# h2oiq_rev1.net
KiCad netlist of a schematic drawn in EAGLE
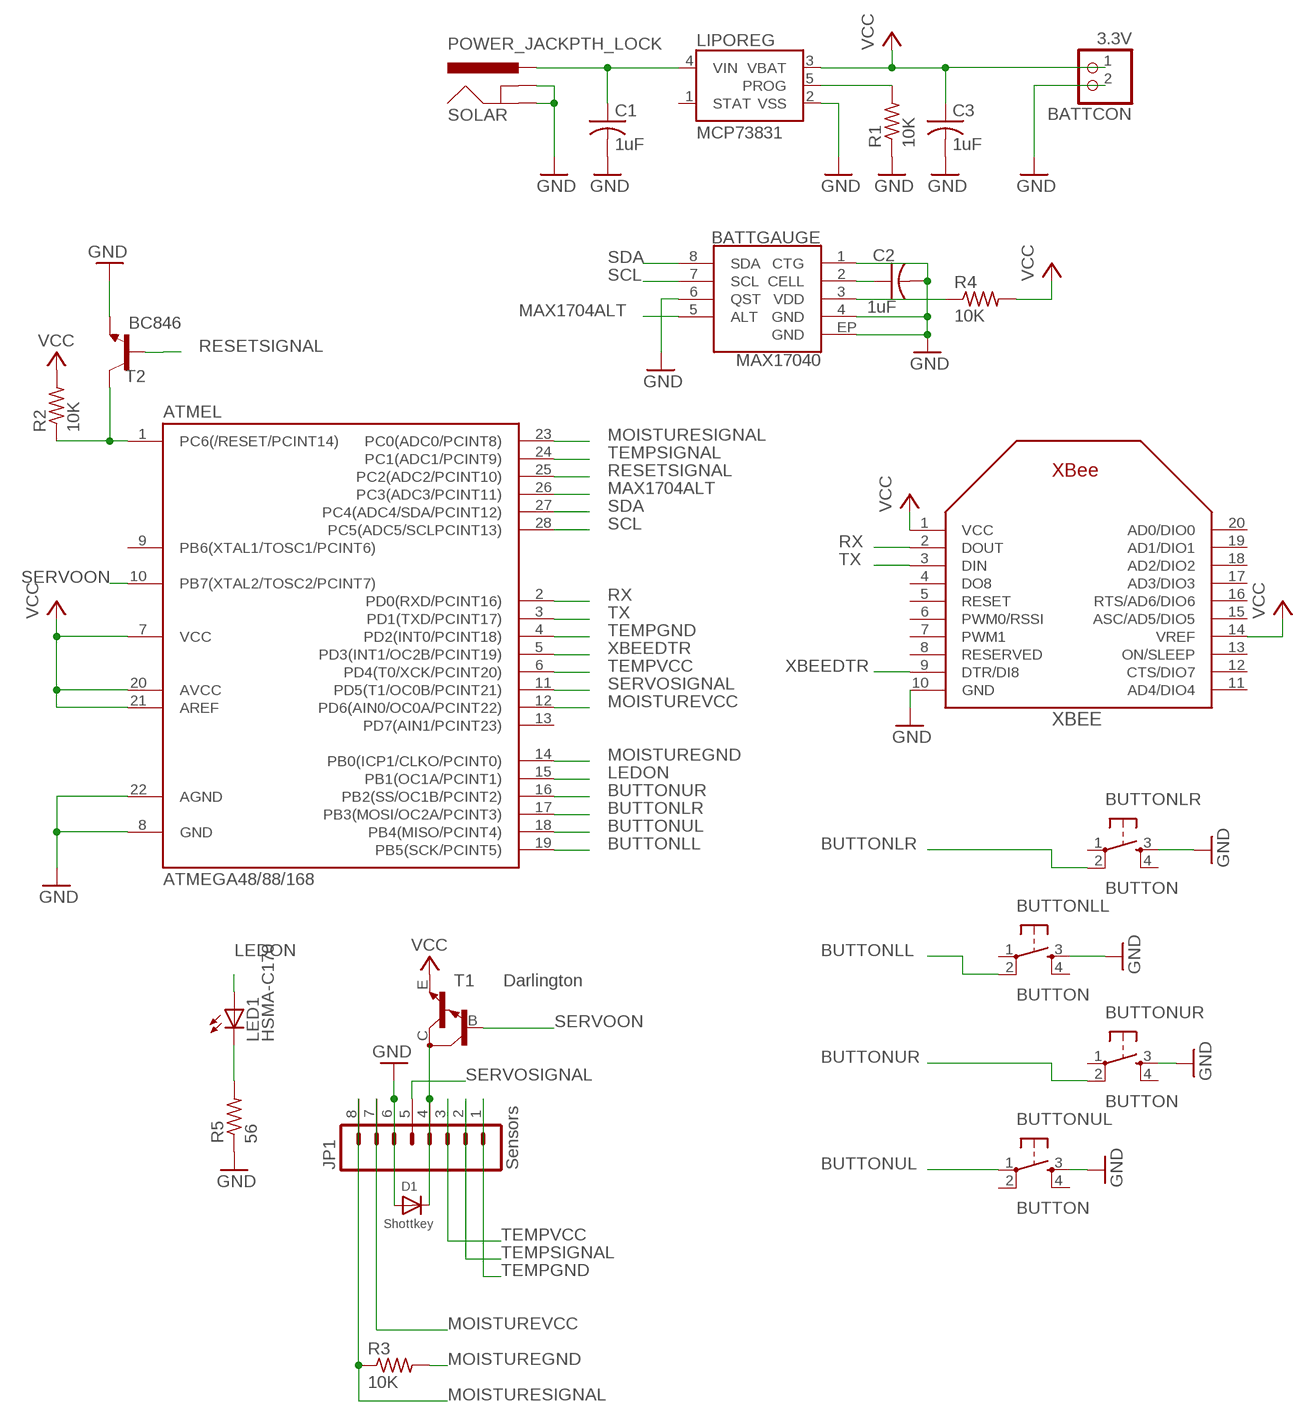
[diagram p0: schematic, sheet 1]

(export (version "E")
  (design (tool "Eeschema 10.0.6"))
  (components
    (comp (ref "ATMEL")
      (value "ATMEGA48/88/168")
      (footprint "eagle-import:DIL28-3")
      (libsource (lib "eagle-import") (part "MEGA48/88/168-PU"))
    )
    (comp (ref "BATTCON")
      (value "3.3V")
      (footprint "eagle-import:JST-PH-2-THM")
      (libsource (lib "eagle-import") (part "JST_2PIN-THM"))
    )
    (comp (ref "BATTGAUGE")
      (value "MAX17040")
      (footprint "eagle-import:MAX17040-TFDN")
      (libsource (lib "eagle-import") (part "MAX17040"))
    )
    (comp (ref "BUTTONLL")
      (value "BUTTON")
      (footprint "eagle-import:TACTILE-PTH")
      (libsource (lib "eagle-import") (part "TAC_SWITCHPTH"))
    )
    (comp (ref "BUTTONLR")
      (value "BUTTON")
      (footprint "eagle-import:TACTILE-PTH")
      (libsource (lib "eagle-import") (part "TAC_SWITCHPTH"))
    )
    (comp (ref "BUTTONUL")
      (value "BUTTON")
      (footprint "eagle-import:TACTILE-PTH")
      (libsource (lib "eagle-import") (part "TAC_SWITCHPTH"))
    )
    (comp (ref "BUTTONUR")
      (value "BUTTON")
      (footprint "eagle-import:TACTILE-PTH")
      (libsource (lib "eagle-import") (part "TAC_SWITCHPTH"))
    )
    (comp (ref "C1")
      (value "1uF")
      (footprint "eagle-import:C0603K")
      (libsource (lib "eagle-import") (part "C-USC0603K"))
    )
    (comp (ref "C2")
      (value "1uF")
      (footprint "eagle-import:C0603K")
      (libsource (lib "eagle-import") (part "C-USC0603K"))
    )
    (comp (ref "C3")
      (value "1uF")
      (footprint "eagle-import:C0603K")
      (libsource (lib "eagle-import") (part "C-USC0603K"))
    )
    (comp (ref "D1")
      (value "Shottkey")
      (footprint "eagle-import:SMADIODE")
      (libsource (lib "eagle-import") (part "DIODESMA"))
    )
    (comp (ref "JP1")
      (value "Sensors")
      (footprint "eagle-import:1X08")
      (libsource (lib "eagle-import") (part "M081X08"))
    )
    (comp (ref "LED1")
      (value "HSMA-C170")
      (footprint "eagle-import:LED-HSMA-SMD")
      (libsource (lib "eagle-import") (part "LED-HSMA-C170"))
    )
    (comp (ref "LIPOREG")
      (value "MCP73831")
      (footprint "eagle-import:SOT23-5")
      (libsource (lib "eagle-import") (part "MCP73831"))
    )
    (comp (ref "R1")
      (value "10K")
      (footprint "eagle-import:R0805")
      (libsource (lib "eagle-import") (part "R-US_R0805"))
    )
    (comp (ref "R2")
      (value "10K")
      (footprint "eagle-import:R0805")
      (libsource (lib "eagle-import") (part "R-US_R0805"))
    )
    (comp (ref "R3")
      (value "10K")
      (footprint "eagle-import:R0805")
      (libsource (lib "eagle-import") (part "R-US_R0805"))
    )
    (comp (ref "R4")
      (value "10K")
      (footprint "eagle-import:R0805")
      (libsource (lib "eagle-import") (part "R-US_R0805"))
    )
    (comp (ref "R5")
      (value "56")
      (footprint "eagle-import:R0805")
      (libsource (lib "eagle-import") (part "R-US_R0805"))
    )
    (comp (ref "SOLAR")
      (value "POWER_JACKPTH_LOCK")
      (footprint "eagle-import:POWER_JACK_PTH_LOCK")
      (libsource (lib "eagle-import") (part "POWER_JACKPTH_LOCK"))
    )
    (comp (ref "T1")
      (value "Darlington")
      (footprint "eagle-import:SOT23-BEC")
      (libsource (lib "eagle-import") (part "-NPN_DARL-SOT23-BECMMBTA13LT1"))
    )
    (comp (ref "T2")
      (value "BC846")
      (footprint "eagle-import:SOT23")
      (libsource (lib "eagle-import") (part "BC846"))
    )
    (comp (ref "XBEE")
      (value "XBEE")
      (footprint "eagle-import:XBEE")
      (libsource (lib "eagle-import") (part "XBEE"))
    )
  )
  (nets
    (net (code "1") (name "/BUTTONLL") (class "Default")
      (node (ref "ATMEL") (pin "19") (pinfunction "PB5(SCK/PCINT5)_19") (pintype "bidirectional"))
      (node (ref "BUTTONLL") (pin "2") (pinfunction "2_2") (pintype "passive"))
    )
    (net (code "2") (name "/BUTTONLR") (class "Default")
      (node (ref "ATMEL") (pin "17") (pinfunction "PB3(MOSI/OC2A/PCINT3)_17") (pintype "bidirectional"))
      (node (ref "BUTTONLR") (pin "2") (pinfunction "2_2") (pintype "passive"))
    )
    (net (code "3") (name "/BUTTONUL") (class "Default")
      (node (ref "ATMEL") (pin "18") (pinfunction "PB4(MISO/PCINT4)_18") (pintype "bidirectional"))
      (node (ref "BUTTONUL") (pin "1") (pinfunction "1_1") (pintype "passive"))
    )
    (net (code "4") (name "/BUTTONUR") (class "Default")
      (node (ref "ATMEL") (pin "16") (pinfunction "PB2(SS/OC1B/PCINT2)_16") (pintype "bidirectional"))
      (node (ref "BUTTONUR") (pin "2") (pinfunction "2_2") (pintype "passive"))
    )
    (net (code "5") (name "/LEDON") (class "Default")
      (node (ref "ATMEL") (pin "15") (pinfunction "PB1(OC1A/PCINT1)_15") (pintype "bidirectional"))
      (node (ref "LED1") (pin "P$1") (pinfunction "A_P$1") (pintype "passive"))
    )
    (net (code "6") (name "/MAX1704ALT") (class "Default")
      (node (ref "ATMEL") (pin "26") (pinfunction "PC3(ADC3/PCINT11)_26") (pintype "bidirectional"))
      (node (ref "BATTGAUGE") (pin "5") (pinfunction "ALT_5") (pintype "bidirectional"))
    )
    (net (code "7") (name "/MOISTUREGND") (class "Default")
      (node (ref "ATMEL") (pin "14") (pinfunction "PB0(ICP1/CLKO/PCINT0)_14") (pintype "bidirectional"))
      (node (ref "R3") (pin "2") (pinfunction "2_2") (pintype "passive"))
    )
    (net (code "8") (name "/MOISTURESIGNAL") (class "Default")
      (node (ref "ATMEL") (pin "23") (pinfunction "PC0(ADC0/PCINT8)_23") (pintype "bidirectional"))
      (node (ref "JP1") (pin "8") (pinfunction "8_8") (pintype "passive"))
      (node (ref "R3") (pin "1") (pinfunction "1_1") (pintype "passive"))
    )
    (net (code "9") (name "/MOISTUREVCC") (class "Default")
      (node (ref "ATMEL") (pin "12") (pinfunction "PD6(AIN0/OC0A/PCINT22)_12") (pintype "bidirectional"))
      (node (ref "JP1") (pin "7") (pinfunction "7_7") (pintype "passive"))
    )
    (net (code "10") (name "/RESETSIGNAL") (class "Default")
      (node (ref "ATMEL") (pin "25") (pinfunction "PC2(ADC2/PCINT10)_25") (pintype "bidirectional"))
      (node (ref "T2") (pin "1") (pinfunction "B_1") (pintype "passive"))
    )
    (net (code "11") (name "/RX") (class "Default")
      (node (ref "ATMEL") (pin "2") (pinfunction "PD0(RXD/PCINT16)_2") (pintype "bidirectional"))
      (node (ref "XBEE") (pin "2") (pinfunction "DOUT_2") (pintype "output"))
    )
    (net (code "12") (name "/SCL") (class "Default")
      (node (ref "ATMEL") (pin "28") (pinfunction "PC5(ADC5/SCLPCINT13)_28") (pintype "bidirectional"))
      (node (ref "BATTGAUGE") (pin "7") (pinfunction "SCL_7") (pintype "bidirectional"))
    )
    (net (code "13") (name "/SDA") (class "Default")
      (node (ref "ATMEL") (pin "27") (pinfunction "PC4(ADC4/SDA/PCINT12)_27") (pintype "bidirectional"))
      (node (ref "BATTGAUGE") (pin "8") (pinfunction "SDA_8") (pintype "bidirectional"))
    )
    (net (code "14") (name "/SERVOON") (class "Default")
      (node (ref "ATMEL") (pin "10") (pinfunction "PB7(XTAL2/TOSC2/PCINT7)_10") (pintype "bidirectional"))
      (node (ref "T1") (pin "B") (pinfunction "B_B") (pintype "passive"))
    )
    (net (code "15") (name "/SERVOSIGNAL") (class "Default")
      (node (ref "ATMEL") (pin "11") (pinfunction "PD5(T1/OC0B/PCINT21)_11") (pintype "bidirectional"))
      (node (ref "JP1") (pin "5") (pinfunction "5_5") (pintype "passive"))
    )
    (net (code "16") (name "/TEMPGND") (class "Default")
      (node (ref "ATMEL") (pin "4") (pinfunction "PD2(INT0/PCINT18)_4") (pintype "bidirectional"))
      (node (ref "JP1") (pin "1") (pinfunction "1_1") (pintype "passive"))
    )
    (net (code "17") (name "/TEMPSIGNAL") (class "Default")
      (node (ref "ATMEL") (pin "24") (pinfunction "PC1(ADC1/PCINT9)_24") (pintype "bidirectional"))
      (node (ref "JP1") (pin "2") (pinfunction "2_2") (pintype "passive"))
    )
    (net (code "18") (name "/TEMPVCC") (class "Default")
      (node (ref "ATMEL") (pin "6") (pinfunction "PD4(T0/XCK/PCINT20)_6") (pintype "bidirectional"))
      (node (ref "JP1") (pin "3") (pinfunction "3_3") (pintype "passive"))
    )
    (net (code "19") (name "/TX") (class "Default")
      (node (ref "ATMEL") (pin "3") (pinfunction "PD1(TXD/PCINT17)_3") (pintype "bidirectional"))
      (node (ref "XBEE") (pin "3") (pinfunction "DIN_3") (pintype "input"))
    )
    (net (code "20") (name "/XBEEDTR") (class "Default")
      (node (ref "ATMEL") (pin "5") (pinfunction "PD3(INT1/OC2B/PCINT19)_5") (pintype "bidirectional"))
      (node (ref "XBEE") (pin "9") (pinfunction "DTR/DI8_9") (pintype "input"))
    )
    (net (code "21") (name "GND") (class "Default")
      (node (ref "ATMEL") (pin "22") (pinfunction "AGND_22") (pintype "power_in"))
      (node (ref "ATMEL") (pin "8") (pinfunction "GND_8") (pintype "power_in"))
      (node (ref "BATTCON") (pin "2") (pinfunction "1_2") (pintype "passive"))
      (node (ref "BATTGAUGE") (pin "1") (pinfunction "CTG_1") (pintype "bidirectional"))
      (node (ref "BATTGAUGE") (pin "4") (pinfunction "GND_4") (pintype "bidirectional"))
      (node (ref "BATTGAUGE") (pin "6") (pinfunction "QST_6") (pintype "bidirectional"))
      (node (ref "BATTGAUGE") (pin "EP") (pinfunction "GND_EP") (pintype "bidirectional"))
      (node (ref "BUTTONLL") (pin "3") (pinfunction "3_3") (pintype "passive"))
      (node (ref "BUTTONLR") (pin "3") (pinfunction "3_3") (pintype "passive"))
      (node (ref "BUTTONUL") (pin "3") (pinfunction "3_3") (pintype "passive"))
      (node (ref "BUTTONUR") (pin "3") (pinfunction "3_3") (pintype "passive"))
      (node (ref "C1") (pin "2") (pinfunction "2_2") (pintype "passive"))
      (node (ref "C2") (pin "2") (pinfunction "2_2") (pintype "passive"))
      (node (ref "C3") (pin "2") (pinfunction "2_2") (pintype "passive"))
      (node (ref "D1") (pin "A") (pinfunction "A_A") (pintype "passive"))
      (node (ref "JP1") (pin "6") (pinfunction "6_6") (pintype "passive"))
      (node (ref "LIPOREG") (pin "2") (pinfunction "VSS_2") (pintype "power_in"))
      (node (ref "R1") (pin "1") (pinfunction "1_1") (pintype "passive"))
      (node (ref "R5") (pin "1") (pinfunction "1_1") (pintype "passive"))
      (node (ref "SOLAR") (pin "GND") (pinfunction "GND_GND") (pintype "bidirectional"))
      (node (ref "SOLAR") (pin "GNDBREAK") (pinfunction "GNDBREAK_GNDBREAK") (pintype "bidirectional"))
      (node (ref "T2") (pin "2") (pinfunction "E_2") (pintype "passive"))
      (node (ref "XBEE") (pin "10") (pinfunction "GND_10") (pintype "power_in"))
    )
    (net (code "22") (name "Net-(ATMEL-PC6({slash}RESET{slash}PCINT14))") (class "Default")
      (node (ref "ATMEL") (pin "1") (pinfunction "PC6(/RESET/PCINT14)_1") (pintype "bidirectional"))
      (node (ref "R2") (pin "1") (pinfunction "1_1") (pintype "passive"))
      (node (ref "T2") (pin "3") (pinfunction "C_3") (pintype "passive"))
    )
    (net (code "23") (name "Net-(BATTGAUGE-CELL)") (class "Default")
      (node (ref "BATTGAUGE") (pin "2") (pinfunction "CELL_2") (pintype "bidirectional"))
      (node (ref "C2") (pin "1") (pinfunction "1_1") (pintype "passive"))
    )
    (net (code "24") (name "Net-(BATTGAUGE-VDD)") (class "Default")
      (node (ref "BATTGAUGE") (pin "3") (pinfunction "VDD_3") (pintype "bidirectional"))
      (node (ref "R4") (pin "1") (pinfunction "1_1") (pintype "passive"))
    )
    (net (code "25") (name "Net-(D1-PadC)") (class "Default")
      (node (ref "D1") (pin "C") (pinfunction "C_C") (pintype "passive"))
      (node (ref "JP1") (pin "4") (pinfunction "4_4") (pintype "passive"))
      (node (ref "T1") (pin "C") (pinfunction "C_C") (pintype "passive"))
    )
    (net (code "26") (name "Net-(LED1-C)") (class "Default")
      (node (ref "LED1") (pin "P$2") (pinfunction "C_P$2") (pintype "passive"))
      (node (ref "R5") (pin "2") (pinfunction "2_2") (pintype "passive"))
    )
    (net (code "27") (name "Net-(LIPOREG-PROG)") (class "Default")
      (node (ref "LIPOREG") (pin "5") (pinfunction "PROG_5") (pintype "input"))
      (node (ref "R1") (pin "2") (pinfunction "2_2") (pintype "passive"))
    )
    (net (code "28") (name "Net-(LIPOREG-VIN)") (class "Default")
      (node (ref "C1") (pin "1") (pinfunction "1_1") (pintype "passive"))
      (node (ref "LIPOREG") (pin "4") (pinfunction "VIN_4") (pintype "power_in"))
      (node (ref "SOLAR") (pin "PWR") (pinfunction "PWR_PWR") (pintype "bidirectional"))
    )
    (net (code "29") (name "VCC") (class "Default")
      (node (ref "ATMEL") (pin "20") (pinfunction "AVCC_20") (pintype "passive"))
      (node (ref "ATMEL") (pin "21") (pinfunction "AREF_21") (pintype "passive"))
      (node (ref "ATMEL") (pin "7") (pinfunction "VCC_7") (pintype "power_in"))
      (node (ref "BATTCON") (pin "1") (pinfunction "2_1") (pintype "passive"))
      (node (ref "C3") (pin "1") (pinfunction "1_1") (pintype "passive"))
      (node (ref "LIPOREG") (pin "3") (pinfunction "VBAT_3") (pintype "power_in"))
      (node (ref "R2") (pin "2") (pinfunction "2_2") (pintype "passive"))
      (node (ref "R4") (pin "2") (pinfunction "2_2") (pintype "passive"))
      (node (ref "T1") (pin "E") (pinfunction "E_E") (pintype "passive"))
      (node (ref "XBEE") (pin "1") (pinfunction "VCC_1") (pintype "power_in"))
      (node (ref "XBEE") (pin "14") (pinfunction "VREF_14") (pintype "input"))
    )
    (net (code "30") (name "unconnected-(ATMEL-PB6(XTAL1{slash}TOSC1{slash}PCINT6)-Pad9)") (class "Default")
      (node (ref "ATMEL") (pin "9") (pinfunction "PB6(XTAL1/TOSC1/PCINT6)_9") (pintype "bidirectional"))
    )
    (net (code "31") (name "unconnected-(ATMEL-PD7(AIN1{slash}PCINT23)-Pad13)") (class "Default")
      (node (ref "ATMEL") (pin "13") (pinfunction "PD7(AIN1/PCINT23)_13") (pintype "bidirectional"))
    )
    (net (code "32") (name "unconnected-(BUTTONLL-Pad1)") (class "Default")
      (node (ref "BUTTONLL") (pin "1") (pinfunction "1_1") (pintype "passive"))
    )
    (net (code "33") (name "unconnected-(BUTTONLL-Pad4)") (class "Default")
      (node (ref "BUTTONLL") (pin "4") (pinfunction "4_4") (pintype "passive"))
    )
    (net (code "34") (name "unconnected-(BUTTONLR-Pad1)") (class "Default")
      (node (ref "BUTTONLR") (pin "1") (pinfunction "1_1") (pintype "passive"))
    )
    (net (code "35") (name "unconnected-(BUTTONLR-Pad4)") (class "Default")
      (node (ref "BUTTONLR") (pin "4") (pinfunction "4_4") (pintype "passive"))
    )
    (net (code "36") (name "unconnected-(BUTTONUL-Pad2)") (class "Default")
      (node (ref "BUTTONUL") (pin "2") (pinfunction "2_2") (pintype "passive"))
    )
    (net (code "37") (name "unconnected-(BUTTONUL-Pad4)") (class "Default")
      (node (ref "BUTTONUL") (pin "4") (pinfunction "4_4") (pintype "passive"))
    )
    (net (code "38") (name "unconnected-(BUTTONUR-Pad1)") (class "Default")
      (node (ref "BUTTONUR") (pin "1") (pinfunction "1_1") (pintype "passive"))
    )
    (net (code "39") (name "unconnected-(BUTTONUR-Pad4)") (class "Default")
      (node (ref "BUTTONUR") (pin "4") (pinfunction "4_4") (pintype "passive"))
    )
    (net (code "40") (name "unconnected-(LIPOREG-STAT-Pad1)") (class "Default")
      (node (ref "LIPOREG") (pin "1") (pinfunction "STAT_1") (pintype "output"))
    )
    (net (code "41") (name "unconnected-(XBEE-AD0{slash}DIO0-Pad20)") (class "Default")
      (node (ref "XBEE") (pin "20") (pinfunction "AD0/DIO0_20") (pintype "bidirectional"))
    )
    (net (code "42") (name "unconnected-(XBEE-AD1{slash}DIO1-Pad19)") (class "Default")
      (node (ref "XBEE") (pin "19") (pinfunction "AD1/DIO1_19") (pintype "bidirectional"))
    )
    (net (code "43") (name "unconnected-(XBEE-AD2{slash}DIO2-Pad18)") (class "Default")
      (node (ref "XBEE") (pin "18") (pinfunction "AD2/DIO2_18") (pintype "bidirectional"))
    )
    (net (code "44") (name "unconnected-(XBEE-AD3{slash}DIO3-Pad17)") (class "Default")
      (node (ref "XBEE") (pin "17") (pinfunction "AD3/DIO3_17") (pintype "bidirectional"))
    )
    (net (code "45") (name "unconnected-(XBEE-AD4{slash}DIO4-Pad11)") (class "Default")
      (node (ref "XBEE") (pin "11") (pinfunction "AD4/DIO4_11") (pintype "bidirectional"))
    )
    (net (code "46") (name "unconnected-(XBEE-ASC{slash}AD5{slash}DIO5-Pad15)") (class "Default")
      (node (ref "XBEE") (pin "15") (pinfunction "ASC/AD5/DIO5_15") (pintype "bidirectional"))
    )
    (net (code "47") (name "unconnected-(XBEE-CTS{slash}DIO7-Pad12)") (class "Default")
      (node (ref "XBEE") (pin "12") (pinfunction "CTS/DIO7_12") (pintype "bidirectional"))
    )
    (net (code "48") (name "unconnected-(XBEE-DO8-Pad4)") (class "Default")
      (node (ref "XBEE") (pin "4") (pinfunction "DO8_4") (pintype "output"))
    )
    (net (code "49") (name "unconnected-(XBEE-ON{slash}SLEEP-Pad13)") (class "Default")
      (node (ref "XBEE") (pin "13") (pinfunction "ON/SLEEP_13") (pintype "output"))
    )
    (net (code "50") (name "unconnected-(XBEE-PWM0{slash}RSSI-Pad6)") (class "Default")
      (node (ref "XBEE") (pin "6") (pinfunction "PWM0/RSSI_6") (pintype "output"))
    )
    (net (code "51") (name "unconnected-(XBEE-PWM1-Pad7)") (class "Default")
      (node (ref "XBEE") (pin "7") (pinfunction "PWM1_7") (pintype "output"))
    )
    (net (code "52") (name "unconnected-(XBEE-RESERVED-Pad8)") (class "Default")
      (node (ref "XBEE") (pin "8") (pinfunction "RESERVED_8") (pintype "no_connect"))
    )
    (net (code "53") (name "unconnected-(XBEE-RESET-Pad5)") (class "Default")
      (node (ref "XBEE") (pin "5") (pinfunction "RESET_5") (pintype "input"))
    )
    (net (code "54") (name "unconnected-(XBEE-RTS{slash}AD6{slash}DIO6-Pad16)") (class "Default")
      (node (ref "XBEE") (pin "16") (pinfunction "RTS/AD6/DIO6_16") (pintype "bidirectional"))
    )
  )
)
